# AAR.net
KiCad netlist of a schematic drawn in EasyEDA Pro
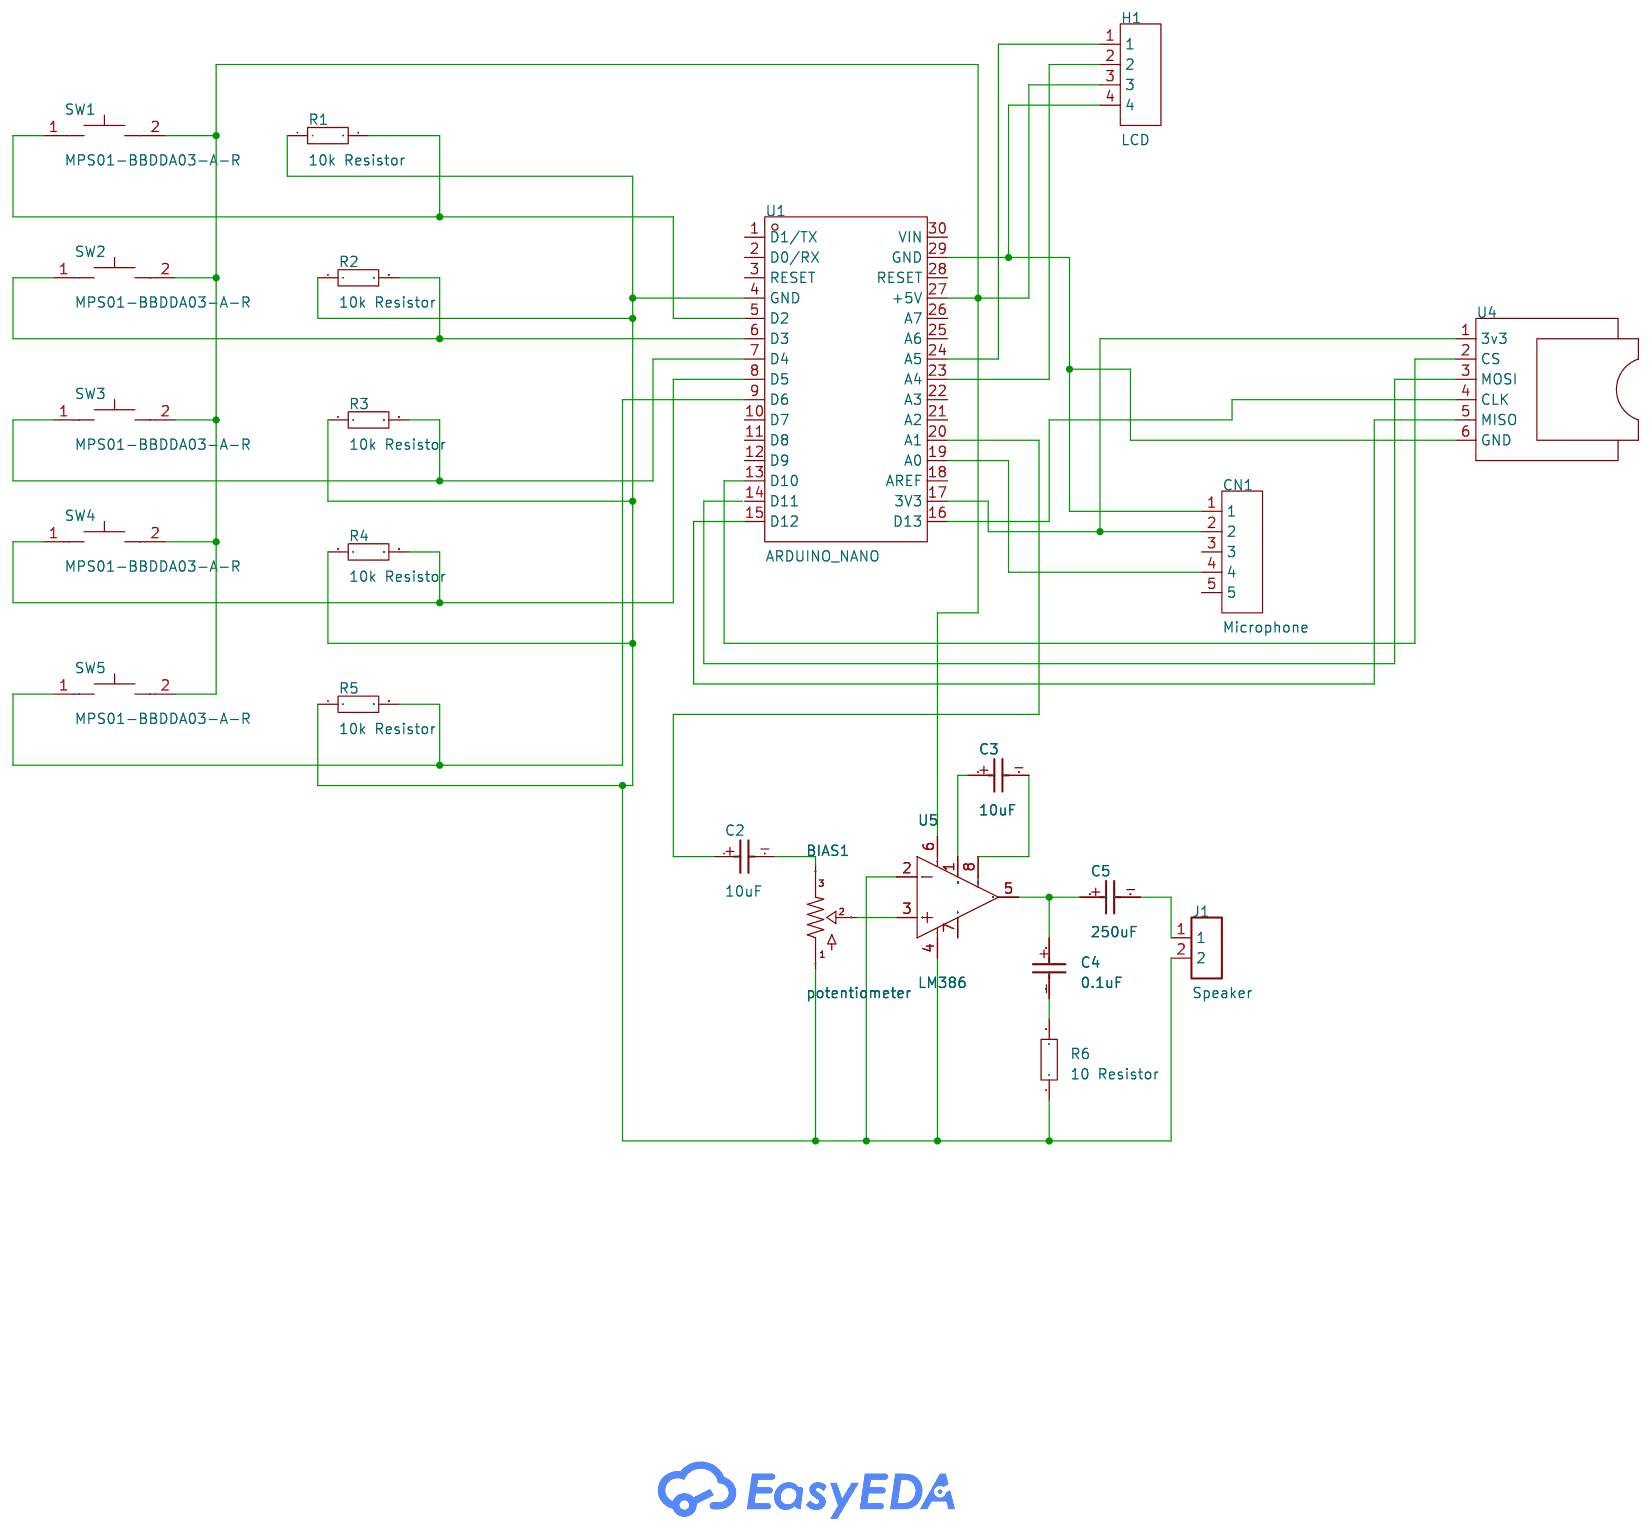
[diagram p0: schematic sheet]

(export (version "E")
  (design (tool "Eeschema 10.0.6"))
  (components
    (comp (ref "BIAS1")
      (value "potentiometer")
      (footprint "easyedapro:TRIM1")
      (libsource (lib "easyedapro") (part "potentiometers_TRIMMER_"))
    )
    (comp (ref "C2")
      (value "10uF")
      (footprint "easyedapro:CAP-TH_L7.2-W2.5-P5.00-D0.5_224CL0016")
      (description "1000microfarad Capacitor")
      (fields
        (field (name "Manufacturer Part") "CL21B104KCFNNNE")
        (field (name "Manufacturer") "SAMSUNG(三星)")
      )
      (libsource (lib "easyedapro") (part "ESY108M035AL4AA"))
    )
    (comp (ref "C3")
      (value "10uF")
      (footprint "easyedapro:CAP-TH_L7.2-W2.5-P5.00-D0.5_224CL0016")
      (description "1000microfarad Capacitor")
      (fields
        (field (name "Manufacturer Part") "CL21B104KCFNNNE")
        (field (name "Manufacturer") "SAMSUNG(三星)")
      )
      (libsource (lib "easyedapro") (part "ESY108M035AL4AA"))
    )
    (comp (ref "C4")
      (value "0.1uF")
      (footprint "easyedapro:CAP-TH_L7.2-W2.5-P5.00-D0.5_224CL0016")
      (description "1000microfarad Capacitor")
      (fields
        (field (name "Manufacturer Part") "CL21B104KCFNNNE")
        (field (name "Manufacturer") "SAMSUNG(三星)")
      )
      (libsource (lib "easyedapro") (part "ESY108M035AL4AA"))
    )
    (comp (ref "C5")
      (value "250uF")
      (footprint "easyedapro:CAP-TH_L7.2-W2.5-P5.00-D0.5_224CL0016")
      (description "1000microfarad Capacitor")
      (fields
        (field (name "Manufacturer Part") "CL21B104KCFNNNE")
        (field (name "Manufacturer") "SAMSUNG(三星)")
      )
      (libsource (lib "easyedapro") (part "ESY108M035AL4AA"))
    )
    (comp (ref "CN1")
      (value "Microphone")
      (footprint "easyedapro:CONN-TH_5P-P1.25_C9900015777")
      (fields (field (name "Manufacturer Part") "按键接插件"))
      (libsource (lib "easyedapro") (part "按键接插件"))
    )
    (comp (ref "H1")
      (value "LCD")
      (footprint "easyedapro:HDR-SMD_4P-P2.54_POGOPIN")
      (fields (field (name "Manufacturer Part") "POGOPIN"))
      (libsource (lib "easyedapro") (part "POGOPIN"))
    )
    (comp (ref "J1")
      (value "Speaker")
      (footprint "easyedapro:JST-PH-2.0-2P")
      (libsource (lib "easyedapro") (part "JST-PH-2.0-2P"))
    )
    (comp (ref "R1")
      (value "10k Resistor")
      (footprint "easyedapro:Resistor 1/8w 7mm metal film")
      (fields
        (field (name "Manufacturer Part") "1206W4F1002T5E")
        (field (name "Manufacturer") "UNI-ROYAL(Uniroyal Elec)")
      )
      (libsource (lib "easyedapro") (part "resistor"))
    )
    (comp (ref "R2")
      (value "10k Resistor")
      (footprint "easyedapro:Resistor 1/8w 7mm metal film")
      (fields
        (field (name "Manufacturer Part") "1206W4F1002T5E")
        (field (name "Manufacturer") "UNI-ROYAL(Uniroyal Elec)")
      )
      (libsource (lib "easyedapro") (part "resistor"))
    )
    (comp (ref "R3")
      (value "10k Resistor")
      (footprint "easyedapro:Resistor 1/8w 7mm metal film")
      (fields
        (field (name "Manufacturer Part") "1206W4F1002T5E")
        (field (name "Manufacturer") "UNI-ROYAL(Uniroyal Elec)")
      )
      (libsource (lib "easyedapro") (part "resistor"))
    )
    (comp (ref "R4")
      (value "10k Resistor")
      (footprint "easyedapro:Resistor 1/8w 7mm metal film")
      (fields
        (field (name "Manufacturer Part") "1206W4F1002T5E")
        (field (name "Manufacturer") "UNI-ROYAL(Uniroyal Elec)")
      )
      (libsource (lib "easyedapro") (part "resistor"))
    )
    (comp (ref "R5")
      (value "10k Resistor")
      (footprint "easyedapro:Resistor 1/8w 7mm metal film")
      (fields
        (field (name "Manufacturer Part") "1206W4F1002T5E")
        (field (name "Manufacturer") "UNI-ROYAL(Uniroyal Elec)")
      )
      (libsource (lib "easyedapro") (part "resistor"))
    )
    (comp (ref "R6")
      (value "10 Resistor")
      (footprint "easyedapro:Resistor 1/8w 7mm metal film")
      (fields
        (field (name "Manufacturer Part") "1206W4F1002T5E")
        (field (name "Manufacturer") "UNI-ROYAL(Uniroyal Elec)")
      )
      (libsource (lib "easyedapro") (part "resistor"))
    )
    (comp (ref "SW1")
      (value "MPS01-BBDDA03-A-R")
      (footprint "easyedapro:SW-TH_MPS01-BBDDA03-A-R")
      (fields (field (name "Manufacturer") "Legion(六钧)"))
      (libsource (lib "easyedapro") (part "MPS01-BBDDA03-A-R"))
    )
    (comp (ref "SW2")
      (value "MPS01-BBDDA03-A-R")
      (footprint "easyedapro:SW-TH_MPS01-BBDDA03-A-R")
      (fields (field (name "Manufacturer") "Legion(六钧)"))
      (libsource (lib "easyedapro") (part "MPS01-BBDDA03-A-R"))
    )
    (comp (ref "SW3")
      (value "MPS01-BBDDA03-A-R")
      (footprint "easyedapro:SW-TH_MPS01-BBDDA03-A-R")
      (fields (field (name "Manufacturer") "Legion(六钧)"))
      (libsource (lib "easyedapro") (part "MPS01-BBDDA03-A-R"))
    )
    (comp (ref "SW4")
      (value "MPS01-BBDDA03-A-R")
      (footprint "easyedapro:SW-TH_MPS01-BBDDA03-A-R")
      (fields (field (name "Manufacturer") "Legion(六钧)"))
      (libsource (lib "easyedapro") (part "MPS01-BBDDA03-A-R"))
    )
    (comp (ref "SW5")
      (value "MPS01-BBDDA03-A-R")
      (footprint "easyedapro:SW-TH_MPS01-BBDDA03-A-R")
      (fields (field (name "Manufacturer") "Legion(六钧)"))
      (libsource (lib "easyedapro") (part "MPS01-BBDDA03-A-R"))
    )
    (comp (ref "U1")
      (value "ARDUINO_NANO")
      (footprint "easyedapro:COMM-TH_ARDUINO_NANO")
      (libsource (lib "easyedapro") (part "ARDUINO_NANO"))
    )
    (comp (ref "U4")
      (value "~")
      (footprint "easyedapro:MicroSD_Module")
      (libsource (lib "easyedapro") (part "MicroSD Module"))
    )
    (comp (ref "U5")
      (value "LM386")
      (footprint "easyedapro:DIP08")
      (libsource (lib "easyedapro") (part "LM386"))
    )
  )
  (nets
    (net (code "1") (name "Net-(BIAS1-Pad3)") (class "Default")
      (node (ref "BIAS1") (pin "3") (pinfunction "3_3") (pintype "unspecified"))
      (node (ref "C2") (pin "2") (pinfunction "2_2") (pintype "input"))
    )
    (net (code "2") (name "Net-(C4-Pad2)") (class "Default")
      (node (ref "C4") (pin "2") (pinfunction "2_2") (pintype "input"))
      (node (ref "R6") (pin "2") (pinfunction "2_2") (pintype "input"))
    )
    (net (code "3") (name "Net-(C5-Pad2)") (class "Default")
      (node (ref "C5") (pin "2") (pinfunction "2_2") (pintype "input"))
      (node (ref "J1") (pin "1") (pinfunction "1_1") (pintype "unspecified"))
    )
    (net (code "4") (name "Net-(U1-+5V)") (class "Default")
      (node (ref "H1") (pin "3") (pinfunction "3_3") (pintype "unspecified"))
      (node (ref "SW1") (pin "2") (pinfunction "2_2") (pintype "unspecified"))
      (node (ref "SW2") (pin "2") (pinfunction "2_2") (pintype "unspecified"))
      (node (ref "SW3") (pin "2") (pinfunction "2_2") (pintype "unspecified"))
      (node (ref "SW4") (pin "2") (pinfunction "2_2") (pintype "unspecified"))
      (node (ref "SW5") (pin "2") (pinfunction "2_2") (pintype "unspecified"))
      (node (ref "U1") (pin "27") (pinfunction "+5V_27") (pintype "unspecified"))
      (node (ref "U5") (pin "6") (pinfunction "V+_6") (pintype "unspecified"))
    )
    (net (code "5") (name "Net-(U1-3V3)") (class "Default")
      (node (ref "CN1") (pin "2") (pinfunction "2_2") (pintype "unspecified"))
      (node (ref "U1") (pin "17") (pinfunction "3V3_17") (pintype "unspecified"))
      (node (ref "U4") (pin "1") (pinfunction "3v3_1") (pintype "input"))
    )
    (net (code "6") (name "Net-(U1-A0)") (class "Default")
      (node (ref "CN1") (pin "4") (pinfunction "4_4") (pintype "unspecified"))
      (node (ref "U1") (pin "19") (pinfunction "A0_19") (pintype "unspecified"))
    )
    (net (code "7") (name "Net-(U1-A1)") (class "Default")
      (node (ref "C2") (pin "1") (pinfunction "1_1") (pintype "input"))
      (node (ref "U1") (pin "20") (pinfunction "A1_20") (pintype "unspecified"))
    )
    (net (code "8") (name "Net-(U1-A4)") (class "Default")
      (node (ref "H1") (pin "2") (pinfunction "2_2") (pintype "unspecified"))
      (node (ref "U1") (pin "23") (pinfunction "A4_23") (pintype "unspecified"))
    )
    (net (code "9") (name "Net-(U1-A5)") (class "Default")
      (node (ref "H1") (pin "1") (pinfunction "1_1") (pintype "unspecified"))
      (node (ref "U1") (pin "24") (pinfunction "A5_24") (pintype "unspecified"))
    )
    (net (code "10") (name "Net-(U1-D2)") (class "Default")
      (node (ref "R1") (pin "2") (pinfunction "2_2") (pintype "input"))
      (node (ref "SW1") (pin "1") (pinfunction "1_1") (pintype "unspecified"))
      (node (ref "U1") (pin "5") (pinfunction "D2_5") (pintype "unspecified"))
    )
    (net (code "11") (name "Net-(U1-D3)") (class "Default")
      (node (ref "R2") (pin "2") (pinfunction "2_2") (pintype "input"))
      (node (ref "SW2") (pin "1") (pinfunction "1_1") (pintype "unspecified"))
      (node (ref "U1") (pin "6") (pinfunction "D3_6") (pintype "unspecified"))
    )
    (net (code "12") (name "Net-(U1-D4)") (class "Default")
      (node (ref "R3") (pin "2") (pinfunction "2_2") (pintype "input"))
      (node (ref "SW3") (pin "1") (pinfunction "1_1") (pintype "unspecified"))
      (node (ref "U1") (pin "7") (pinfunction "D4_7") (pintype "unspecified"))
    )
    (net (code "13") (name "Net-(U1-D5)") (class "Default")
      (node (ref "R4") (pin "2") (pinfunction "2_2") (pintype "input"))
      (node (ref "SW4") (pin "1") (pinfunction "1_1") (pintype "unspecified"))
      (node (ref "U1") (pin "8") (pinfunction "D5_8") (pintype "unspecified"))
    )
    (net (code "14") (name "Net-(U1-D6)") (class "Default")
      (node (ref "R5") (pin "2") (pinfunction "2_2") (pintype "input"))
      (node (ref "SW5") (pin "1") (pinfunction "1_1") (pintype "unspecified"))
      (node (ref "U1") (pin "9") (pinfunction "D6_9") (pintype "unspecified"))
    )
    (net (code "15") (name "Net-(U1-D10)") (class "Default")
      (node (ref "U1") (pin "13") (pinfunction "D10_13") (pintype "unspecified"))
      (node (ref "U4") (pin "2") (pinfunction "CS_2") (pintype "input"))
    )
    (net (code "16") (name "Net-(U1-D12)") (class "Default")
      (node (ref "U1") (pin "15") (pinfunction "D12_15") (pintype "unspecified"))
      (node (ref "U4") (pin "5") (pinfunction "MISO_5") (pintype "input"))
    )
    (net (code "17") (name "Net-(U1-D13)") (class "Default")
      (node (ref "U1") (pin "16") (pinfunction "D13_16") (pintype "unspecified"))
      (node (ref "U4") (pin "4") (pinfunction "CLK_4") (pintype "input"))
    )
    (net (code "18") (name "Net-(U4-GND)") (class "Default")
      (node (ref "CN1") (pin "1") (pinfunction "1_1") (pintype "unspecified"))
      (node (ref "H1") (pin "4") (pinfunction "4_4") (pintype "unspecified"))
      (node (ref "U1") (pin "29") (pinfunction "GND_29") (pintype "unspecified"))
      (node (ref "U4") (pin "6") (pinfunction "GND_6") (pintype "input"))
    )
    (net (code "19") (name "Net-(U5-+IN)") (class "Default")
      (node (ref "BIAS1") (pin "2") (pinfunction "2_2") (pintype "unspecified"))
      (node (ref "U5") (pin "3") (pinfunction "+IN_3") (pintype "input"))
    )
    (net (code "20") (name "Net-(U5--IN)") (class "Default")
      (node (ref "BIAS1") (pin "1") (pinfunction "1_1") (pintype "unspecified"))
      (node (ref "J1") (pin "2") (pinfunction "2_2") (pintype "unspecified"))
      (node (ref "R1") (pin "1") (pinfunction "1_1") (pintype "input"))
      (node (ref "R2") (pin "1") (pinfunction "1_1") (pintype "input"))
      (node (ref "R3") (pin "1") (pinfunction "1_1") (pintype "input"))
      (node (ref "R4") (pin "1") (pinfunction "1_1") (pintype "input"))
      (node (ref "R5") (pin "1") (pinfunction "1_1") (pintype "input"))
      (node (ref "R6") (pin "1") (pinfunction "1_1") (pintype "input"))
      (node (ref "U1") (pin "4") (pinfunction "GND_4") (pintype "unspecified"))
      (node (ref "U5") (pin "2") (pinfunction "-IN_2") (pintype "input"))
      (node (ref "U5") (pin "4") (pinfunction "V-_4") (pintype "unspecified"))
    )
    (net (code "21") (name "Net-(U5-GAIN@1)") (class "Default")
      (node (ref "C3") (pin "1") (pinfunction "1_1") (pintype "input"))
      (node (ref "U5") (pin "1") (pinfunction "GAIN@1_1") (pintype "bidirectional"))
    )
    (net (code "22") (name "Net-(U5-GAIN@8)") (class "Default")
      (node (ref "C3") (pin "2") (pinfunction "2_2") (pintype "input"))
      (node (ref "U5") (pin "8") (pinfunction "GAIN@8_8") (pintype "bidirectional"))
    )
    (net (code "23") (name "Net-(U5-OUT)") (class "Default")
      (node (ref "C4") (pin "1") (pinfunction "1_1") (pintype "input"))
      (node (ref "C5") (pin "1") (pinfunction "1_1") (pintype "input"))
      (node (ref "U5") (pin "5") (pinfunction "OUT_5") (pintype "output"))
    )
    (net (code "24") (name "unconnected-(CN1-Pad3)") (class "Default")
      (node (ref "CN1") (pin "3") (pinfunction "3_3") (pintype "unspecified"))
    )
    (net (code "25") (name "unconnected-(CN1-Pad5)") (class "Default")
      (node (ref "CN1") (pin "5") (pinfunction "5_5") (pintype "unspecified"))
    )
    (net (code "26") (name "unconnected-(U1-A2-Pad21)") (class "Default")
      (node (ref "U1") (pin "21") (pinfunction "A2_21") (pintype "unspecified"))
    )
    (net (code "27") (name "unconnected-(U1-A3-Pad22)") (class "Default")
      (node (ref "U1") (pin "22") (pinfunction "A3_22") (pintype "unspecified"))
    )
    (net (code "28") (name "unconnected-(U1-A6-Pad25)") (class "Default")
      (node (ref "U1") (pin "25") (pinfunction "A6_25") (pintype "unspecified"))
    )
    (net (code "29") (name "unconnected-(U1-A7-Pad26)") (class "Default")
      (node (ref "U1") (pin "26") (pinfunction "A7_26") (pintype "unspecified"))
    )
    (net (code "30") (name "unconnected-(U1-AREF-Pad18)") (class "Default")
      (node (ref "U1") (pin "18") (pinfunction "AREF_18") (pintype "unspecified"))
    )
    (net (code "31") (name "unconnected-(U1-D0{slash}RX-Pad2)") (class "Default")
      (node (ref "U1") (pin "2") (pinfunction "D0/RX_2") (pintype "unspecified"))
    )
    (net (code "32") (name "unconnected-(U1-D1{slash}TX-Pad1)") (class "Default")
      (node (ref "U1") (pin "1") (pinfunction "D1/TX_1") (pintype "unspecified"))
    )
    (net (code "33") (name "unconnected-(U1-D7-Pad10)") (class "Default")
      (node (ref "U1") (pin "10") (pinfunction "D7_10") (pintype "unspecified"))
    )
    (net (code "34") (name "unconnected-(U1-D8-Pad11)") (class "Default")
      (node (ref "U1") (pin "11") (pinfunction "D8_11") (pintype "unspecified"))
    )
    (net (code "35") (name "unconnected-(U1-D9-Pad12)") (class "Default")
      (node (ref "U1") (pin "12") (pinfunction "D9_12") (pintype "unspecified"))
    )
    (net (code "36") (name "unconnected-(U1-D11-Pad14)") (class "Default")
      (node (ref "U1") (pin "14") (pinfunction "D11_14") (pintype "unspecified"))
    )
    (net (code "37") (name "unconnected-(U1-RESET-Pad3)") (class "Default")
      (node (ref "U1") (pin "3") (pinfunction "RESET_3") (pintype "unspecified"))
    )
    (net (code "38") (name "unconnected-(U1-RESET-Pad28)") (class "Default")
      (node (ref "U1") (pin "28") (pinfunction "RESET_28") (pintype "unspecified"))
    )
    (net (code "39") (name "unconnected-(U1-VIN-Pad30)") (class "Default")
      (node (ref "U1") (pin "30") (pinfunction "VIN_30") (pintype "unspecified"))
    )
    (net (code "40") (name "unconnected-(U4-MOSI-Pad3)") (class "Default")
      (node (ref "U4") (pin "3") (pinfunction "MOSI_3") (pintype "input"))
    )
    (net (code "41") (name "unconnected-(U5-BP-Pad7)") (class "Default")
      (node (ref "U5") (pin "7") (pinfunction "BP_7") (pintype "bidirectional"))
    )
  )
)
